# Sheet1.net
KiCad netlist of a schematic drawn in Altium Designer
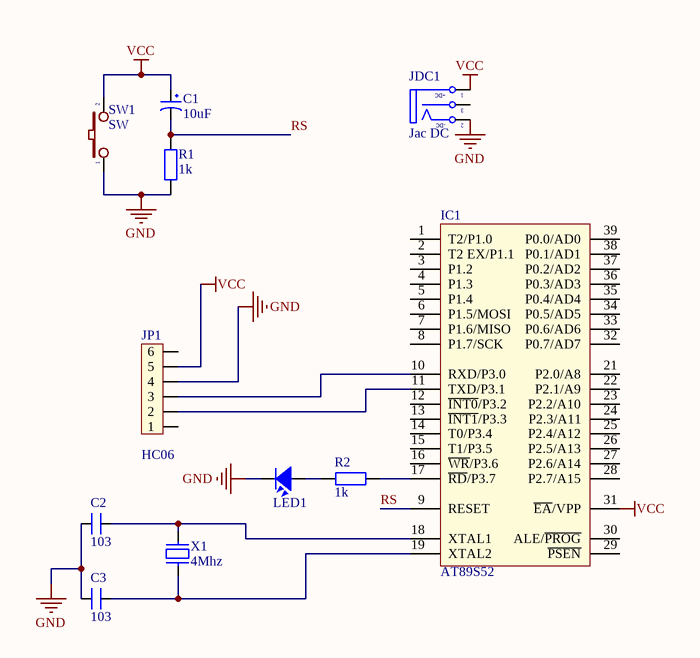
[diagram p0: Sheet1.SchDoc]

(export (version "E")
  (design (tool "Eeschema 10.0.6"))
  (components
    (comp (ref "C1")
      (value "10uF")
      (footprint "CP1/2")
      (description "Cap P  0,1uF < 22uF , 16 - 50V")
      (libsource (lib "syhaunguyen") (part "CP1"))
    )
    (comp (ref "C2")
      (value "103")
      (footprint "CN1.5")
      (description "Cap np 682pF => 104pF")
      (libsource (lib "syhaunguyen") (part "CN1.5"))
    )
    (comp (ref "C3")
      (value "103")
      (footprint "CN1.5")
      (description "Cap np 682pF => 104pF")
      (libsource (lib "syhaunguyen") (part "CN1.5"))
    )
    (comp (ref "IC1")
      (value "AT89S52")
      (footprint "DIP40/W0.6")
      (description "AT89S52, 8k Byte Flash Memory , 40 Pin")
      (libsource (lib "syhaunguyen") (part "AT89S52"))
    )
    (comp (ref "JDC1")
      (value "Jac DC")
      (footprint "DC-IN")
      (description "Jac DC input")
      (libsource (lib "syhaunguyen") (part "DCIN"))
    )
    (comp (ref "JP1")
      (value "HC06")
      (footprint "JP6")
      (description "JP6 PIN")
      (libsource (lib "syhaunguyen") (part "JP6"))
    )
    (comp (ref "LED1")
      (value "LED")
      (footprint "LED-3")
      (description "LED Single colour Green and Red")
      (libsource (lib "syhaunguyen") (part "LED"))
    )
    (comp (ref "R1")
      (value "1k")
      (footprint "R1/4W")
      (description "Resistor 1/4W")
      (libsource (lib "syhaunguyen") (part "R1/4W"))
    )
    (comp (ref "R2")
      (value "1k")
      (footprint "R1/4W")
      (description "Resistor 1/4W")
      (libsource (lib "syhaunguyen") (part "R1/4W"))
    )
    (comp (ref "SW1")
      (value "SW")
      (footprint "SW2")
      (description "Switch button 2 pin")
      (libsource (lib "syhaunguyen") (part "SW2"))
    )
    (comp (ref "X1")
      (value "4Mhz")
      (footprint "XT2")
      (description "Crystal For all Crystal 2pin.")
      (libsource (lib "hphonglib") (part "XT2"))
    )
  )
  (nets
    (net (code "1") (name "/RS") (class "Default")
      (node (ref "C1") (pin "2") (pinfunction "2_2") (pintype "passive"))
      (node (ref "IC1") (pin "9") (pinfunction "RESET_9") (pintype "passive"))
      (node (ref "R1") (pin "2") (pinfunction "2_2") (pintype "passive"))
    )
    (net (code "2") (name "GND") (class "Default")
      (node (ref "C2") (pin "1") (pinfunction "1_1") (pintype "passive"))
      (node (ref "C3") (pin "1") (pinfunction "1_1") (pintype "passive"))
      (node (ref "IC1") (pin "20") (pinfunction "GND_20") (pintype "power_in"))
      (node (ref "JDC1") (pin "2") (pinfunction "TN_2") (pintype "passive"))
      (node (ref "JP1") (pin "4") (pinfunction "4_4") (pintype "passive"))
      (node (ref "LED1") (pin "2") (pinfunction "2_2") (pintype "passive"))
      (node (ref "R1") (pin "1") (pinfunction "1_1") (pintype "passive"))
      (node (ref "SW1") (pin "1") (pinfunction "1_1") (pintype "passive"))
    )
    (net (code "3") (name "Net-(IC1-RXD{slash}P3.0)") (class "Default")
      (node (ref "IC1") (pin "10") (pinfunction "RXD/P3.0_10") (pintype "passive"))
      (node (ref "JP1") (pin "3") (pinfunction "3_3") (pintype "passive"))
    )
    (net (code "4") (name "Net-(IC1-TXD{slash}P3.1)") (class "Default")
      (node (ref "IC1") (pin "11") (pinfunction "TXD/P3.1_11") (pintype "passive"))
      (node (ref "JP1") (pin "2") (pinfunction "2_2") (pintype "passive"))
    )
    (net (code "5") (name "Net-(IC1-XTAL1)") (class "Default")
      (node (ref "C2") (pin "2") (pinfunction "2_2") (pintype "passive"))
      (node (ref "IC1") (pin "18") (pinfunction "XTAL1_18") (pintype "passive"))
      (node (ref "X1") (pin "1") (pinfunction "1_1") (pintype "passive"))
    )
    (net (code "6") (name "Net-(IC1-XTAL2)") (class "Default")
      (node (ref "C3") (pin "2") (pinfunction "2_2") (pintype "passive"))
      (node (ref "IC1") (pin "19") (pinfunction "XTAL2_19") (pintype "passive"))
      (node (ref "X1") (pin "2") (pinfunction "2_2") (pintype "passive"))
    )
    (net (code "7") (name "Net-(IC1-~{RD}{slash}P3.7)") (class "Default")
      (node (ref "IC1") (pin "17") (pinfunction "~{RD}/P3.7_17") (pintype "passive"))
      (node (ref "R2") (pin "2") (pinfunction "2_2") (pintype "passive"))
    )
    (net (code "8") (name "Net-(LED1-Pad1)") (class "Default")
      (node (ref "LED1") (pin "1") (pinfunction "1_1") (pintype "passive"))
      (node (ref "R2") (pin "1") (pinfunction "1_1") (pintype "passive"))
    )
    (net (code "9") (name "VCC") (class "Default")
      (node (ref "C1") (pin "1") (pinfunction "1_1") (pintype "passive"))
      (node (ref "IC1") (pin "31") (pinfunction "~{EA}/VPP_31") (pintype "passive"))
      (node (ref "IC1") (pin "40") (pinfunction "VCC_40") (pintype "power_in"))
      (node (ref "JDC1") (pin "1") (pinfunction "T_1") (pintype "passive"))
      (node (ref "JP1") (pin "5") (pinfunction "5_5") (pintype "passive"))
      (node (ref "SW1") (pin "2") (pinfunction "2_2") (pintype "passive"))
    )
    (net (code "10") (name "unconnected-(IC1-ALE{slash}~{PROG}-Pad30)") (class "Default")
      (node (ref "IC1") (pin "30") (pinfunction "ALE/~{PROG}_30") (pintype "passive"))
    )
    (net (code "11") (name "unconnected-(IC1-P0.0{slash}AD0-Pad39)") (class "Default")
      (node (ref "IC1") (pin "39") (pinfunction "P0.0/AD0_39") (pintype "passive"))
    )
    (net (code "12") (name "unconnected-(IC1-P0.1{slash}AD1-Pad38)") (class "Default")
      (node (ref "IC1") (pin "38") (pinfunction "P0.1/AD1_38") (pintype "passive"))
    )
    (net (code "13") (name "unconnected-(IC1-P0.2{slash}AD2-Pad37)") (class "Default")
      (node (ref "IC1") (pin "37") (pinfunction "P0.2/AD2_37") (pintype "passive"))
    )
    (net (code "14") (name "unconnected-(IC1-P0.3{slash}AD3-Pad36)") (class "Default")
      (node (ref "IC1") (pin "36") (pinfunction "P0.3/AD3_36") (pintype "passive"))
    )
    (net (code "15") (name "unconnected-(IC1-P0.4{slash}AD4-Pad35)") (class "Default")
      (node (ref "IC1") (pin "35") (pinfunction "P0.4/AD4_35") (pintype "passive"))
    )
    (net (code "16") (name "unconnected-(IC1-P0.5{slash}AD5-Pad34)") (class "Default")
      (node (ref "IC1") (pin "34") (pinfunction "P0.5/AD5_34") (pintype "passive"))
    )
    (net (code "17") (name "unconnected-(IC1-P0.6{slash}AD6-Pad33)") (class "Default")
      (node (ref "IC1") (pin "33") (pinfunction "P0.6/AD6_33") (pintype "passive"))
    )
    (net (code "18") (name "unconnected-(IC1-P0.7{slash}AD7-Pad32)") (class "Default")
      (node (ref "IC1") (pin "32") (pinfunction "P0.7/AD7_32") (pintype "passive"))
    )
    (net (code "19") (name "unconnected-(IC1-P1.2-Pad3)") (class "Default")
      (node (ref "IC1") (pin "3") (pinfunction "P1.2_3") (pintype "passive"))
    )
    (net (code "20") (name "unconnected-(IC1-P1.3-Pad4)") (class "Default")
      (node (ref "IC1") (pin "4") (pinfunction "P1.3_4") (pintype "passive"))
    )
    (net (code "21") (name "unconnected-(IC1-P1.4-Pad5)") (class "Default")
      (node (ref "IC1") (pin "5") (pinfunction "P1.4_5") (pintype "passive"))
    )
    (net (code "22") (name "unconnected-(IC1-P1.5{slash}MOSI-Pad6)") (class "Default")
      (node (ref "IC1") (pin "6") (pinfunction "P1.5/MOSI_6") (pintype "passive"))
    )
    (net (code "23") (name "unconnected-(IC1-P1.6{slash}MISO-Pad7)") (class "Default")
      (node (ref "IC1") (pin "7") (pinfunction "P1.6/MISO_7") (pintype "passive"))
    )
    (net (code "24") (name "unconnected-(IC1-P1.7{slash}SCK-Pad8)") (class "Default")
      (node (ref "IC1") (pin "8") (pinfunction "P1.7/SCK_8") (pintype "passive"))
    )
    (net (code "25") (name "unconnected-(IC1-P2.0{slash}A8-Pad21)") (class "Default")
      (node (ref "IC1") (pin "21") (pinfunction "P2.0/A8_21") (pintype "passive"))
    )
    (net (code "26") (name "unconnected-(IC1-P2.1{slash}A9-Pad22)") (class "Default")
      (node (ref "IC1") (pin "22") (pinfunction "P2.1/A9_22") (pintype "passive"))
    )
    (net (code "27") (name "unconnected-(IC1-P2.2{slash}A10-Pad23)") (class "Default")
      (node (ref "IC1") (pin "23") (pinfunction "P2.2/A10_23") (pintype "passive"))
    )
    (net (code "28") (name "unconnected-(IC1-P2.3{slash}A11-Pad24)") (class "Default")
      (node (ref "IC1") (pin "24") (pinfunction "P2.3/A11_24") (pintype "passive"))
    )
    (net (code "29") (name "unconnected-(IC1-P2.4{slash}A12-Pad25)") (class "Default")
      (node (ref "IC1") (pin "25") (pinfunction "P2.4/A12_25") (pintype "passive"))
    )
    (net (code "30") (name "unconnected-(IC1-P2.5{slash}A13-Pad26)") (class "Default")
      (node (ref "IC1") (pin "26") (pinfunction "P2.5/A13_26") (pintype "passive"))
    )
    (net (code "31") (name "unconnected-(IC1-P2.6{slash}A14-Pad27)") (class "Default")
      (node (ref "IC1") (pin "27") (pinfunction "P2.6/A14_27") (pintype "passive"))
    )
    (net (code "32") (name "unconnected-(IC1-P2.7{slash}A15-Pad28)") (class "Default")
      (node (ref "IC1") (pin "28") (pinfunction "P2.7/A15_28") (pintype "passive"))
    )
    (net (code "33") (name "unconnected-(IC1-T0{slash}P3.4-Pad14)") (class "Default")
      (node (ref "IC1") (pin "14") (pinfunction "T0/P3.4_14") (pintype "passive"))
    )
    (net (code "34") (name "unconnected-(IC1-T1{slash}P3.5-Pad15)") (class "Default")
      (node (ref "IC1") (pin "15") (pinfunction "T1/P3.5_15") (pintype "passive"))
    )
    (net (code "35") (name "unconnected-(IC1-T2_EX{slash}P1.1-Pad2)") (class "Default")
      (node (ref "IC1") (pin "2") (pinfunction "T2_EX/P1.1_2") (pintype "passive"))
    )
    (net (code "36") (name "unconnected-(IC1-T2{slash}P1.0-Pad1)") (class "Default")
      (node (ref "IC1") (pin "1") (pinfunction "T2/P1.0_1") (pintype "passive"))
    )
    (net (code "37") (name "unconnected-(IC1-~{INT0}{slash}P3.2-Pad12)") (class "Default")
      (node (ref "IC1") (pin "12") (pinfunction "~{INT0}/P3.2_12") (pintype "passive"))
    )
    (net (code "38") (name "unconnected-(IC1-~{INT1}{slash}P3.3-Pad13)") (class "Default")
      (node (ref "IC1") (pin "13") (pinfunction "~{INT1}/P3.3_13") (pintype "passive"))
    )
    (net (code "39") (name "unconnected-(IC1-~{PSEN}-Pad29)") (class "Default")
      (node (ref "IC1") (pin "29") (pinfunction "~{PSEN}_29") (pintype "passive"))
    )
    (net (code "40") (name "unconnected-(IC1-~{WR}{slash}P3.6-Pad16)") (class "Default")
      (node (ref "IC1") (pin "16") (pinfunction "~{WR}/P3.6_16") (pintype "passive"))
    )
    (net (code "41") (name "unconnected-(JDC1-S-Pad3)") (class "Default")
      (node (ref "JDC1") (pin "3") (pinfunction "S_3") (pintype "power_in"))
    )
    (net (code "42") (name "unconnected-(JP1-Pad1)") (class "Default")
      (node (ref "JP1") (pin "1") (pinfunction "1_1") (pintype "passive"))
    )
    (net (code "43") (name "unconnected-(JP1-Pad6)") (class "Default")
      (node (ref "JP1") (pin "6") (pinfunction "6_6") (pintype "passive"))
    )
  )
)
